# attiny85.net
KiCad netlist of a schematic drawn in EAGLE
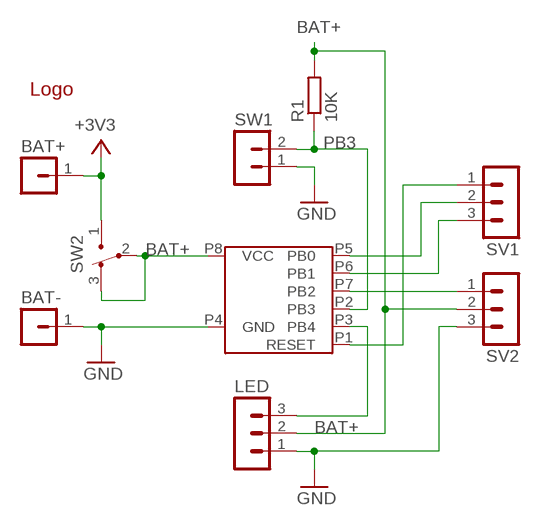
[diagram p0: schematic, sheet 1]

(export (version "E")
  (design (tool "Eeschema 10.0.6"))
  (components
    (comp (ref "ATTINY85-1")
      (value "ATTINY85SOP8")
      (footprint "eagle-import:ATTINY85-20SUR")
      (libsource (lib "eagle-import") (part "ATTINY85SOP8"))
    )
    (comp (ref "BAT+")
      (value "PINHEAD-MA01-1")
      (footprint "eagle-import:PINHEAD-MA01-1")
      (libsource (lib "eagle-import") (part "PINHEAD-MA01-1"))
    )
    (comp (ref "BAT-")
      (value "PINHEAD-MA01-1")
      (footprint "eagle-import:PINHEAD-MA01-1")
      (libsource (lib "eagle-import") (part "PINHEAD-MA01-1"))
    )
    (comp (ref "LED")
      (value "PINHEAD-MA03-1")
      (footprint "eagle-import:PINHEAD-MA03-1")
      (libsource (lib "eagle-import") (part "ytani1_30941153_PINHEAD-MA03-1"))
    )
    (comp (ref "LOGO1")
      (value "LOGO-YTLOGO2-BOTTOM")
      (footprint "eagle-import:LOGO-YT2-BOTTOM")
      (libsource (lib "eagle-import") (part "LOGO-YTLOGO2-BOTTOM"))
    )
    (comp (ref "R1")
      (value "10K")
      (footprint "eagle-import:M3216")
      (libsource (lib "eagle-import") (part "R-EU_M3216"))
    )
    (comp (ref "SV1")
      (value "PINHEAD-MA03-1")
      (footprint "eagle-import:PINHEAD-MA03-1")
      (libsource (lib "eagle-import") (part "PINHEAD-MA03-1"))
    )
    (comp (ref "SV2")
      (value "PINHEAD-MA03-1")
      (footprint "eagle-import:PINHEAD-MA03-1")
      (libsource (lib "eagle-import") (part "PINHEAD-MA03-1"))
    )
    (comp (ref "SW1")
      (value "PINHEAD-MA02-1")
      (footprint "eagle-import:PINHEAD-MA02-1")
      (libsource (lib "eagle-import") (part "PINHEAD-MA02-1"))
    )
    (comp (ref "SW2")
      (value "SW3-1")
      (footprint "eagle-import:SW3-1")
      (fields (field (name "MF") "HiLetgo"))
      (libsource (lib "eagle-import") (part "SW3-1"))
    )
  )
  (nets
    (net (code "1") (name "+3V3") (class "Default")
      (node (ref "BAT+") (pin "1") (pinfunction "1_1") (pintype "passive"))
      (node (ref "SW2") (pin "1") (pinfunction "1_1") (pintype "passive"))
    )
    (net (code "2") (name "/BAT+") (class "Default")
      (node (ref "ATTINY85-1") (pin "P8") (pinfunction "VCC_P8") (pintype "bidirectional"))
      (node (ref "LED") (pin "2") (pinfunction "2_2") (pintype "passive"))
      (node (ref "R1") (pin "2") (pinfunction "2_2") (pintype "passive"))
      (node (ref "SV2") (pin "2") (pinfunction "2_2") (pintype "passive"))
      (node (ref "SW2") (pin "2") (pinfunction "2_2") (pintype "passive"))
      (node (ref "SW2") (pin "3") (pinfunction "3_3") (pintype "passive"))
    )
    (net (code "3") (name "/PB3") (class "Default")
      (node (ref "ATTINY85-1") (pin "P2") (pinfunction "PB3_P2") (pintype "bidirectional"))
      (node (ref "R1") (pin "1") (pinfunction "1_1") (pintype "passive"))
      (node (ref "SW1") (pin "2") (pinfunction "2_2") (pintype "passive"))
    )
    (net (code "4") (name "GND") (class "Default")
      (node (ref "ATTINY85-1") (pin "P4") (pinfunction "GND_P4") (pintype "bidirectional"))
      (node (ref "BAT-") (pin "1") (pinfunction "1_1") (pintype "passive"))
      (node (ref "LED") (pin "1") (pinfunction "1_1") (pintype "passive"))
      (node (ref "SV2") (pin "3") (pinfunction "3_3") (pintype "passive"))
      (node (ref "SW1") (pin "1") (pinfunction "1_1") (pintype "passive"))
    )
    (net (code "5") (name "Net-(ATTINY85-1-PB0)") (class "Default")
      (node (ref "ATTINY85-1") (pin "P5") (pinfunction "PB0_P5") (pintype "bidirectional"))
      (node (ref "SV1") (pin "2") (pinfunction "2_2") (pintype "passive"))
    )
    (net (code "6") (name "Net-(ATTINY85-1-PB1)") (class "Default")
      (node (ref "ATTINY85-1") (pin "P6") (pinfunction "PB1_P6") (pintype "bidirectional"))
      (node (ref "SV1") (pin "3") (pinfunction "3_3") (pintype "passive"))
    )
    (net (code "7") (name "Net-(ATTINY85-1-PB2)") (class "Default")
      (node (ref "ATTINY85-1") (pin "P7") (pinfunction "PB2_P7") (pintype "bidirectional"))
      (node (ref "SV2") (pin "1") (pinfunction "1_1") (pintype "passive"))
    )
    (net (code "8") (name "Net-(ATTINY85-1-PB4)") (class "Default")
      (node (ref "ATTINY85-1") (pin "P3") (pinfunction "PB4_P3") (pintype "bidirectional"))
      (node (ref "LED") (pin "3") (pinfunction "3_3") (pintype "passive"))
    )
    (net (code "9") (name "Net-(ATTINY85-1-RESET)") (class "Default")
      (node (ref "ATTINY85-1") (pin "P1") (pinfunction "RESET_P1") (pintype "bidirectional"))
      (node (ref "SV1") (pin "1") (pinfunction "1_1") (pintype "passive"))
    )
  )
)
